# io.net
KiCad netlist of a schematic drawn in Altium Designer
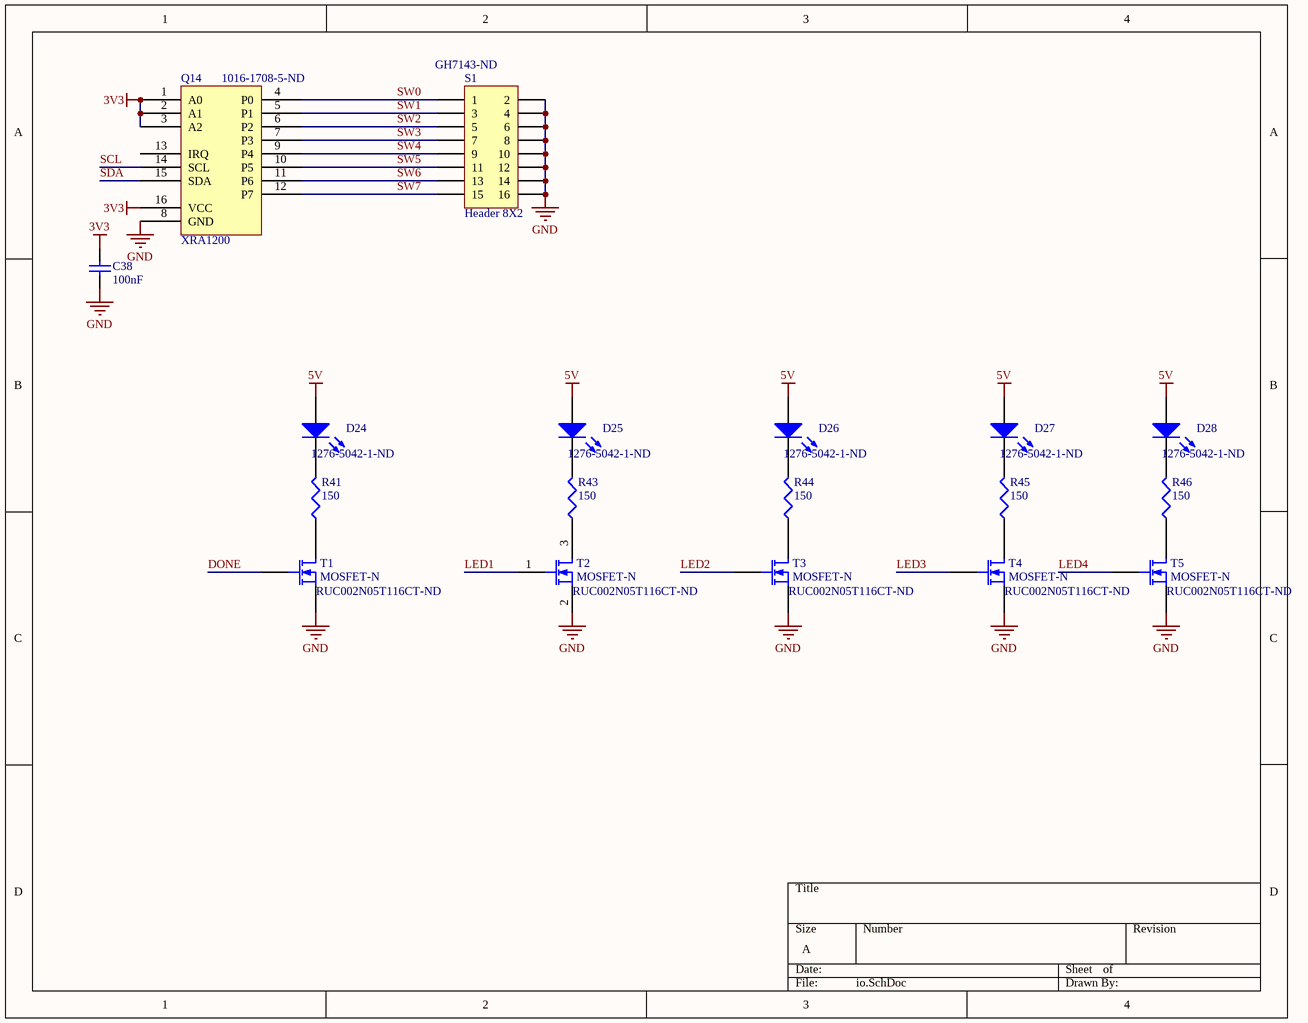
[diagram p0: io.SchDoc]

(export (version "E")
  (design (tool "Eeschema 10.0.6"))
  (components
    (comp (ref "C38")
      (value "100nF")
      (footprint "CAPC1005X06L")
      (description "Capacitor")
      (fields (field (name "Comment") "Cap") (field (name "PUBLISHER") "Altium Limited"))
      (libsource (lib "Miscellaneous Devices") (part "Cap"))
    )
    (comp (ref "D24")
      (value "LED2")
      (footprint "LED-0603")
      (description "Typical RED, GREEN, YELLOW, AMBER GaAs LED")
      (fields (field (name "PUBLISHER") "Altium Limited"))
      (libsource (lib "Miscellaneous Devices") (part "LED2"))
    )
    (comp (ref "D25")
      (value "LED2")
      (footprint "LED-0603")
      (description "Typical RED, GREEN, YELLOW, AMBER GaAs LED")
      (fields (field (name "PUBLISHER") "Altium Limited"))
      (libsource (lib "Miscellaneous Devices") (part "LED2"))
    )
    (comp (ref "D26")
      (value "LED2")
      (footprint "LED-0603")
      (description "Typical RED, GREEN, YELLOW, AMBER GaAs LED")
      (fields (field (name "PUBLISHER") "Altium Limited"))
      (libsource (lib "Miscellaneous Devices") (part "LED2"))
    )
    (comp (ref "D27")
      (value "LED2")
      (footprint "LED-0603")
      (description "Typical RED, GREEN, YELLOW, AMBER GaAs LED")
      (fields (field (name "PUBLISHER") "Altium Limited"))
      (libsource (lib "Miscellaneous Devices") (part "LED2"))
    )
    (comp (ref "D28")
      (value "LED2")
      (footprint "LED-0603")
      (description "Typical RED, GREEN, YELLOW, AMBER GaAs LED")
      (fields (field (name "PUBLISHER") "Altium Limited"))
      (libsource (lib "Miscellaneous Devices") (part "LED2"))
    )
    (comp (ref "Q14")
      (value "XRA1200")
      (footprint "TSOP65P640X120-16N")
      (fields (field (name "SUPPLIER PART NUMBER 1") "1016-1708-5-ND"))
      (libsource (lib "schlib") (part "XRA1200"))
    )
    (comp (ref "R41")
      (value "150")
      (footprint "CAPC1608X90N")
      (description "Resistor")
      (fields
        (field (name "SUPPLIER PART NUMBER 1") "1276-5042-1-ND")
        (field (name "Comment") "Res3")
        (field (name "PUBLISHER") "Altium Limited")
      )
      (libsource (lib "Miscellaneous Devices") (part "Res3"))
    )
    (comp (ref "R43")
      (value "150")
      (footprint "CAPC1608X90N")
      (description "Resistor")
      (fields
        (field (name "SUPPLIER PART NUMBER 1") "1276-5042-1-ND")
        (field (name "Comment") "Res3")
        (field (name "PUBLISHER") "Altium Limited")
      )
      (libsource (lib "Miscellaneous Devices") (part "Res3"))
    )
    (comp (ref "R44")
      (value "150")
      (footprint "CAPC1608X90N")
      (description "Resistor")
      (fields
        (field (name "SUPPLIER PART NUMBER 1") "1276-5042-1-ND")
        (field (name "Comment") "Res3")
        (field (name "PUBLISHER") "Altium Limited")
      )
      (libsource (lib "Miscellaneous Devices") (part "Res3"))
    )
    (comp (ref "R45")
      (value "150")
      (footprint "CAPC1608X90N")
      (description "Resistor")
      (fields
        (field (name "SUPPLIER PART NUMBER 1") "1276-5042-1-ND")
        (field (name "Comment") "Res3")
        (field (name "PUBLISHER") "Altium Limited")
      )
      (libsource (lib "Miscellaneous Devices") (part "Res3"))
    )
    (comp (ref "R46")
      (value "150")
      (footprint "CAPC1608X90N")
      (description "Resistor")
      (fields
        (field (name "SUPPLIER PART NUMBER 1") "1276-5042-1-ND")
        (field (name "Comment") "Res3")
        (field (name "PUBLISHER") "Altium Limited")
      )
      (libsource (lib "Miscellaneous Devices") (part "Res3"))
    )
    (comp (ref "S1")
      (value "Header 8X2")
      (footprint "76PSB08ST")
      (description "Header, 8-Pin, Dual row")
      (fields (field (name "SUPPLIER PART NUMBER 1") "GH7143-ND") (field (name "PUBLISHER") "Altium Limited"))
      (libsource (lib "Miscellaneous Connectors") (part "Header 8X2"))
    )
    (comp (ref "T1")
      (value "MOSFET-N")
      (footprint "SOT23-3")
      (description "N-Channel MOSFET")
      (fields
        (field (name "SUPPLIER PART NUMBER 1") "RUC002N05T116CT-ND")
        (field (name "PUBLISHER") "Altium Limited")
      )
      (libsource (lib "Miscellaneous Devices") (part "MOSFET-N"))
    )
    (comp (ref "T2")
      (value "MOSFET-N")
      (footprint "SOT23-3")
      (description "N-Channel MOSFET")
      (fields
        (field (name "SUPPLIER PART NUMBER 1") "RUC002N05T116CT-ND")
        (field (name "PUBLISHER") "Altium Limited")
      )
      (libsource (lib "") (part "MOSFET-N_1"))
    )
    (comp (ref "T3")
      (value "MOSFET-N")
      (footprint "SOT23-3")
      (description "N-Channel MOSFET")
      (fields
        (field (name "SUPPLIER PART NUMBER 1") "RUC002N05T116CT-ND")
        (field (name "PUBLISHER") "Altium Limited")
      )
      (libsource (lib "Miscellaneous Devices") (part "MOSFET-N"))
    )
    (comp (ref "T4")
      (value "MOSFET-N")
      (footprint "SOT23-3")
      (description "N-Channel MOSFET")
      (fields
        (field (name "SUPPLIER PART NUMBER 1") "RUC002N05T116CT-ND")
        (field (name "PUBLISHER") "Altium Limited")
      )
      (libsource (lib "Miscellaneous Devices") (part "MOSFET-N"))
    )
    (comp (ref "T5")
      (value "MOSFET-N")
      (footprint "SOT23-3")
      (description "N-Channel MOSFET")
      (fields
        (field (name "SUPPLIER PART NUMBER 1") "RUC002N05T116CT-ND")
        (field (name "PUBLISHER") "Altium Limited")
      )
      (libsource (lib "Miscellaneous Devices") (part "MOSFET-N"))
    )
  )
  (nets
    (net (code "1") (name "/DONE") (class "Default")
      (node (ref "T1") (pin "1") (pinfunction "G_1") (pintype "passive"))
    )
    (net (code "2") (name "/LED1") (class "Default")
      (node (ref "T2") (pin "1") (pinfunction "G_1") (pintype "passive"))
    )
    (net (code "3") (name "/LED2") (class "Default")
      (node (ref "T3") (pin "1") (pinfunction "G_1") (pintype "passive"))
    )
    (net (code "4") (name "/LED3") (class "Default")
      (node (ref "T4") (pin "1") (pinfunction "G_1") (pintype "passive"))
    )
    (net (code "5") (name "/LED4") (class "Default")
      (node (ref "T5") (pin "1") (pinfunction "G_1") (pintype "passive"))
    )
    (net (code "6") (name "/SCL") (class "Default")
      (node (ref "Q14") (pin "14") (pinfunction "SCL_14") (pintype "passive"))
    )
    (net (code "7") (name "/SDA") (class "Default")
      (node (ref "Q14") (pin "15") (pinfunction "SDA_15") (pintype "passive"))
    )
    (net (code "8") (name "/SW0") (class "Default")
      (node (ref "Q14") (pin "4") (pinfunction "P0_4") (pintype "passive"))
      (node (ref "S1") (pin "1") (pinfunction "1_1") (pintype "passive"))
    )
    (net (code "9") (name "/SW1") (class "Default")
      (node (ref "Q14") (pin "5") (pinfunction "P1_5") (pintype "passive"))
      (node (ref "S1") (pin "3") (pinfunction "3_3") (pintype "passive"))
    )
    (net (code "10") (name "/SW2") (class "Default")
      (node (ref "Q14") (pin "6") (pinfunction "P2_6") (pintype "passive"))
      (node (ref "S1") (pin "5") (pinfunction "5_5") (pintype "passive"))
    )
    (net (code "11") (name "/SW3") (class "Default")
      (node (ref "Q14") (pin "7") (pinfunction "P3_7") (pintype "passive"))
      (node (ref "S1") (pin "7") (pinfunction "7_7") (pintype "passive"))
    )
    (net (code "12") (name "/SW4") (class "Default")
      (node (ref "Q14") (pin "9") (pinfunction "P4_9") (pintype "passive"))
      (node (ref "S1") (pin "9") (pinfunction "9_9") (pintype "passive"))
    )
    (net (code "13") (name "/SW5") (class "Default")
      (node (ref "Q14") (pin "10") (pinfunction "P5_10") (pintype "passive"))
      (node (ref "S1") (pin "11") (pinfunction "11_11") (pintype "passive"))
    )
    (net (code "14") (name "/SW6") (class "Default")
      (node (ref "Q14") (pin "11") (pinfunction "P6_11") (pintype "passive"))
      (node (ref "S1") (pin "13") (pinfunction "13_13") (pintype "passive"))
    )
    (net (code "15") (name "/SW7") (class "Default")
      (node (ref "Q14") (pin "12") (pinfunction "P7_12") (pintype "passive"))
      (node (ref "S1") (pin "15") (pinfunction "15_15") (pintype "passive"))
    )
    (net (code "16") (name "3V3") (class "Default")
      (node (ref "C38") (pin "2") (pinfunction "2_2") (pintype "passive"))
      (node (ref "Q14") (pin "1") (pinfunction "A0_1") (pintype "passive"))
      (node (ref "Q14") (pin "16") (pinfunction "VCC_16") (pintype "passive"))
      (node (ref "Q14") (pin "2") (pinfunction "A1_2") (pintype "passive"))
      (node (ref "Q14") (pin "3") (pinfunction "A2_3") (pintype "passive"))
    )
    (net (code "17") (name "5V") (class "Default")
      (node (ref "D24") (pin "A") (pinfunction "A_A") (pintype "passive"))
      (node (ref "D25") (pin "A") (pinfunction "A_A") (pintype "passive"))
      (node (ref "D26") (pin "A") (pinfunction "A_A") (pintype "passive"))
      (node (ref "D27") (pin "A") (pinfunction "A_A") (pintype "passive"))
      (node (ref "D28") (pin "A") (pinfunction "A_A") (pintype "passive"))
    )
    (net (code "18") (name "GND") (class "Default")
      (node (ref "C38") (pin "1") (pinfunction "1_1") (pintype "passive"))
      (node (ref "Q14") (pin "8") (pinfunction "GND_8") (pintype "passive"))
      (node (ref "S1") (pin "10") (pinfunction "10_10") (pintype "passive"))
      (node (ref "S1") (pin "12") (pinfunction "12_12") (pintype "passive"))
      (node (ref "S1") (pin "14") (pinfunction "14_14") (pintype "passive"))
      (node (ref "S1") (pin "16") (pinfunction "16_16") (pintype "passive"))
      (node (ref "S1") (pin "2") (pinfunction "2_2") (pintype "passive"))
      (node (ref "S1") (pin "4") (pinfunction "4_4") (pintype "passive"))
      (node (ref "S1") (pin "6") (pinfunction "6_6") (pintype "passive"))
      (node (ref "S1") (pin "8") (pinfunction "8_8") (pintype "passive"))
      (node (ref "T1") (pin "2") (pinfunction "S_2") (pintype "passive"))
      (node (ref "T2") (pin "2") (pinfunction "S_2") (pintype "passive"))
      (node (ref "T3") (pin "2") (pinfunction "S_2") (pintype "passive"))
      (node (ref "T4") (pin "2") (pinfunction "S_2") (pintype "passive"))
      (node (ref "T5") (pin "2") (pinfunction "S_2") (pintype "passive"))
    )
    (net (code "19") (name "Net-(D24-PadK)") (class "Default")
      (node (ref "D24") (pin "K") (pinfunction "K_K") (pintype "passive"))
      (node (ref "R41") (pin "2") (pinfunction "2_2") (pintype "passive"))
    )
    (net (code "20") (name "Net-(D25-PadK)") (class "Default")
      (node (ref "D25") (pin "K") (pinfunction "K_K") (pintype "passive"))
      (node (ref "R43") (pin "2") (pinfunction "2_2") (pintype "passive"))
    )
    (net (code "21") (name "Net-(D26-PadK)") (class "Default")
      (node (ref "D26") (pin "K") (pinfunction "K_K") (pintype "passive"))
      (node (ref "R44") (pin "2") (pinfunction "2_2") (pintype "passive"))
    )
    (net (code "22") (name "Net-(D27-PadK)") (class "Default")
      (node (ref "D27") (pin "K") (pinfunction "K_K") (pintype "passive"))
      (node (ref "R45") (pin "2") (pinfunction "2_2") (pintype "passive"))
    )
    (net (code "23") (name "Net-(D28-PadK)") (class "Default")
      (node (ref "D28") (pin "K") (pinfunction "K_K") (pintype "passive"))
      (node (ref "R46") (pin "2") (pinfunction "2_2") (pintype "passive"))
    )
    (net (code "24") (name "Net-(T1-D)") (class "Default")
      (node (ref "R41") (pin "1") (pinfunction "1_1") (pintype "passive"))
      (node (ref "T1") (pin "3") (pinfunction "D_3") (pintype "passive"))
    )
    (net (code "25") (name "Net-(T2-D)") (class "Default")
      (node (ref "R43") (pin "1") (pinfunction "1_1") (pintype "passive"))
      (node (ref "T2") (pin "3") (pinfunction "D_3") (pintype "passive"))
    )
    (net (code "26") (name "Net-(T3-D)") (class "Default")
      (node (ref "R44") (pin "1") (pinfunction "1_1") (pintype "passive"))
      (node (ref "T3") (pin "3") (pinfunction "D_3") (pintype "passive"))
    )
    (net (code "27") (name "Net-(T4-D)") (class "Default")
      (node (ref "R45") (pin "1") (pinfunction "1_1") (pintype "passive"))
      (node (ref "T4") (pin "3") (pinfunction "D_3") (pintype "passive"))
    )
    (net (code "28") (name "Net-(T5-D)") (class "Default")
      (node (ref "R46") (pin "1") (pinfunction "1_1") (pintype "passive"))
      (node (ref "T5") (pin "3") (pinfunction "D_3") (pintype "passive"))
    )
    (net (code "29") (name "unconnected-(Q14-IRQ-Pad13)") (class "Default")
      (node (ref "Q14") (pin "13") (pinfunction "IRQ_13") (pintype "passive"))
    )
  )
)
